# usbswitch.net
KiCad netlist of a schematic drawn in EAGLE
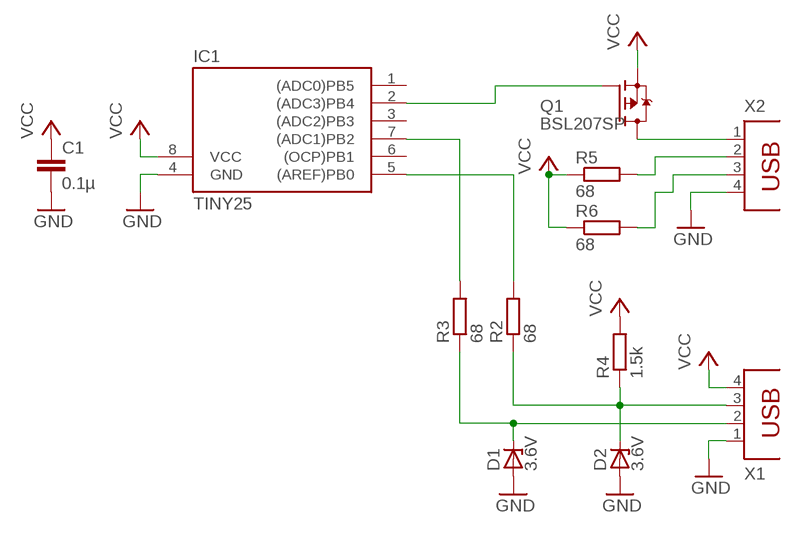
[diagram p0: schematic, sheet 1]

(export (version "E")
  (design (tool "Eeschema 10.0.6"))
  (components
    (comp (ref "C1")
      (value "0.1µ")
      (footprint "eagle-import:C1206")
      (libsource (lib "eagle-import") (part "C-EUC1206"))
    )
    (comp (ref "D1")
      (value "3.6V")
      (footprint "eagle-import:SOD80C")
      (libsource (lib "eagle-import") (part "ZENER-DIODESOD80C"))
    )
    (comp (ref "D2")
      (value "3.6V")
      (footprint "eagle-import:SOD80C")
      (libsource (lib "eagle-import") (part "ZENER-DIODESOD80C"))
    )
    (comp (ref "IC1")
      (value "TINY25")
      (footprint "eagle-import:SOIC8")
      (libsource (lib "eagle-import") (part "TINY15LS"))
    )
    (comp (ref "Q1")
      (value "BSL207SP")
      (footprint "eagle-import:SOT23")
      (libsource (lib "eagle-import") (part "BSL207SP"))
    )
    (comp (ref "R2")
      (value "68")
      (footprint "eagle-import:R1206")
      (libsource (lib "eagle-import") (part "R-EU_R1206"))
    )
    (comp (ref "R3")
      (value "68")
      (footprint "eagle-import:R1206")
      (libsource (lib "eagle-import") (part "R-EU_R1206"))
    )
    (comp (ref "R4")
      (value "1.5k")
      (footprint "eagle-import:R1206")
      (libsource (lib "eagle-import") (part "R-EU_R1206"))
    )
    (comp (ref "R5")
      (value "68")
      (footprint "eagle-import:R1206@1")
      (libsource (lib "eagle-import") (part "resistor_R-EU_R1206"))
    )
    (comp (ref "R6")
      (value "68")
      (footprint "eagle-import:R1206")
      (libsource (lib "eagle-import") (part "R-EU_R1206"))
    )
    (comp (ref "X1")
      (value "PN87520")
      (footprint "eagle-import:PN87520")
      (libsource (lib "eagle-import") (part "PN87520"))
    )
    (comp (ref "X2")
      (value "PN87520")
      (footprint "eagle-import:PN87520")
      (libsource (lib "eagle-import") (part "PN87520"))
    )
  )
  (nets
    (net (code "1") (name "GND") (class "Default")
      (node (ref "C1") (pin "2") (pinfunction "2_2") (pintype "passive"))
      (node (ref "D1") (pin "A") (pinfunction "A_A") (pintype "passive"))
      (node (ref "D2") (pin "A") (pinfunction "A_A") (pintype "passive"))
      (node (ref "IC1") (pin "4") (pinfunction "GND_4") (pintype "power_in"))
      (node (ref "X1") (pin "1") (pinfunction "1_1") (pintype "passive"))
      (node (ref "X2") (pin "4") (pinfunction "4_4") (pintype "passive"))
    )
    (net (code "2") (name "Net-(D1-PadC)") (class "Default")
      (node (ref "D1") (pin "C") (pinfunction "C_C") (pintype "passive"))
      (node (ref "R3") (pin "1") (pinfunction "1_1") (pintype "passive"))
      (node (ref "X1") (pin "2") (pinfunction "2_2") (pintype "passive"))
    )
    (net (code "3") (name "Net-(D2-PadC)") (class "Default")
      (node (ref "D2") (pin "C") (pinfunction "C_C") (pintype "passive"))
      (node (ref "R2") (pin "1") (pinfunction "1_1") (pintype "passive"))
      (node (ref "R4") (pin "1") (pinfunction "1_1") (pintype "passive"))
      (node (ref "X1") (pin "3") (pinfunction "3_3") (pintype "passive"))
    )
    (net (code "4") (name "Net-(IC1-(ADC1)PB2)") (class "Default")
      (node (ref "IC1") (pin "7") (pinfunction "(ADC1)PB2_7") (pintype "bidirectional"))
      (node (ref "R3") (pin "2") (pinfunction "2_2") (pintype "passive"))
    )
    (net (code "5") (name "Net-(IC1-(ADC3)PB4)") (class "Default")
      (node (ref "IC1") (pin "2") (pinfunction "(ADC3)PB4_2") (pintype "bidirectional"))
      (node (ref "Q1") (pin "1") (pinfunction "G_1") (pintype "passive"))
    )
    (net (code "6") (name "Net-(IC1-(AREF)PB0)") (class "Default")
      (node (ref "IC1") (pin "5") (pinfunction "(AREF)PB0_5") (pintype "bidirectional"))
      (node (ref "R2") (pin "2") (pinfunction "2_2") (pintype "passive"))
    )
    (net (code "7") (name "Net-(Q1-D)") (class "Default")
      (node (ref "Q1") (pin "3") (pinfunction "D_3") (pintype "passive"))
      (node (ref "X2") (pin "1") (pinfunction "1_1") (pintype "passive"))
    )
    (net (code "8") (name "Net-(R5-Pad2)") (class "Default")
      (node (ref "R5") (pin "2") (pinfunction "2_2") (pintype "passive"))
      (node (ref "X2") (pin "2") (pinfunction "2_2") (pintype "passive"))
    )
    (net (code "9") (name "Net-(R6-Pad2)") (class "Default")
      (node (ref "R6") (pin "2") (pinfunction "2_2") (pintype "passive"))
      (node (ref "X2") (pin "3") (pinfunction "3_3") (pintype "passive"))
    )
    (net (code "10") (name "VCC") (class "Default")
      (node (ref "C1") (pin "1") (pinfunction "1_1") (pintype "passive"))
      (node (ref "IC1") (pin "8") (pinfunction "VCC_8") (pintype "power_in"))
      (node (ref "Q1") (pin "2") (pinfunction "S_2") (pintype "passive"))
      (node (ref "R4") (pin "2") (pinfunction "2_2") (pintype "passive"))
      (node (ref "R5") (pin "1") (pinfunction "1_1") (pintype "passive"))
      (node (ref "R6") (pin "1") (pinfunction "1_1") (pintype "passive"))
      (node (ref "X1") (pin "4") (pinfunction "4_4") (pintype "passive"))
    )
    (net (code "11") (name "unconnected-(IC1-(ADC0)PB5-Pad1)") (class "Default")
      (node (ref "IC1") (pin "1") (pinfunction "(ADC0)PB5_1") (pintype "bidirectional"))
    )
    (net (code "12") (name "unconnected-(IC1-(ADC2)PB3-Pad3)") (class "Default")
      (node (ref "IC1") (pin "3") (pinfunction "(ADC2)PB3_3") (pintype "bidirectional"))
    )
    (net (code "13") (name "unconnected-(IC1-(OCP)PB1-Pad6)") (class "Default")
      (node (ref "IC1") (pin "6") (pinfunction "(OCP)PB1_6") (pintype "bidirectional"))
    )
  )
)
